# BATT_INPUT.net
KiCad netlist of a schematic drawn in EAGLE
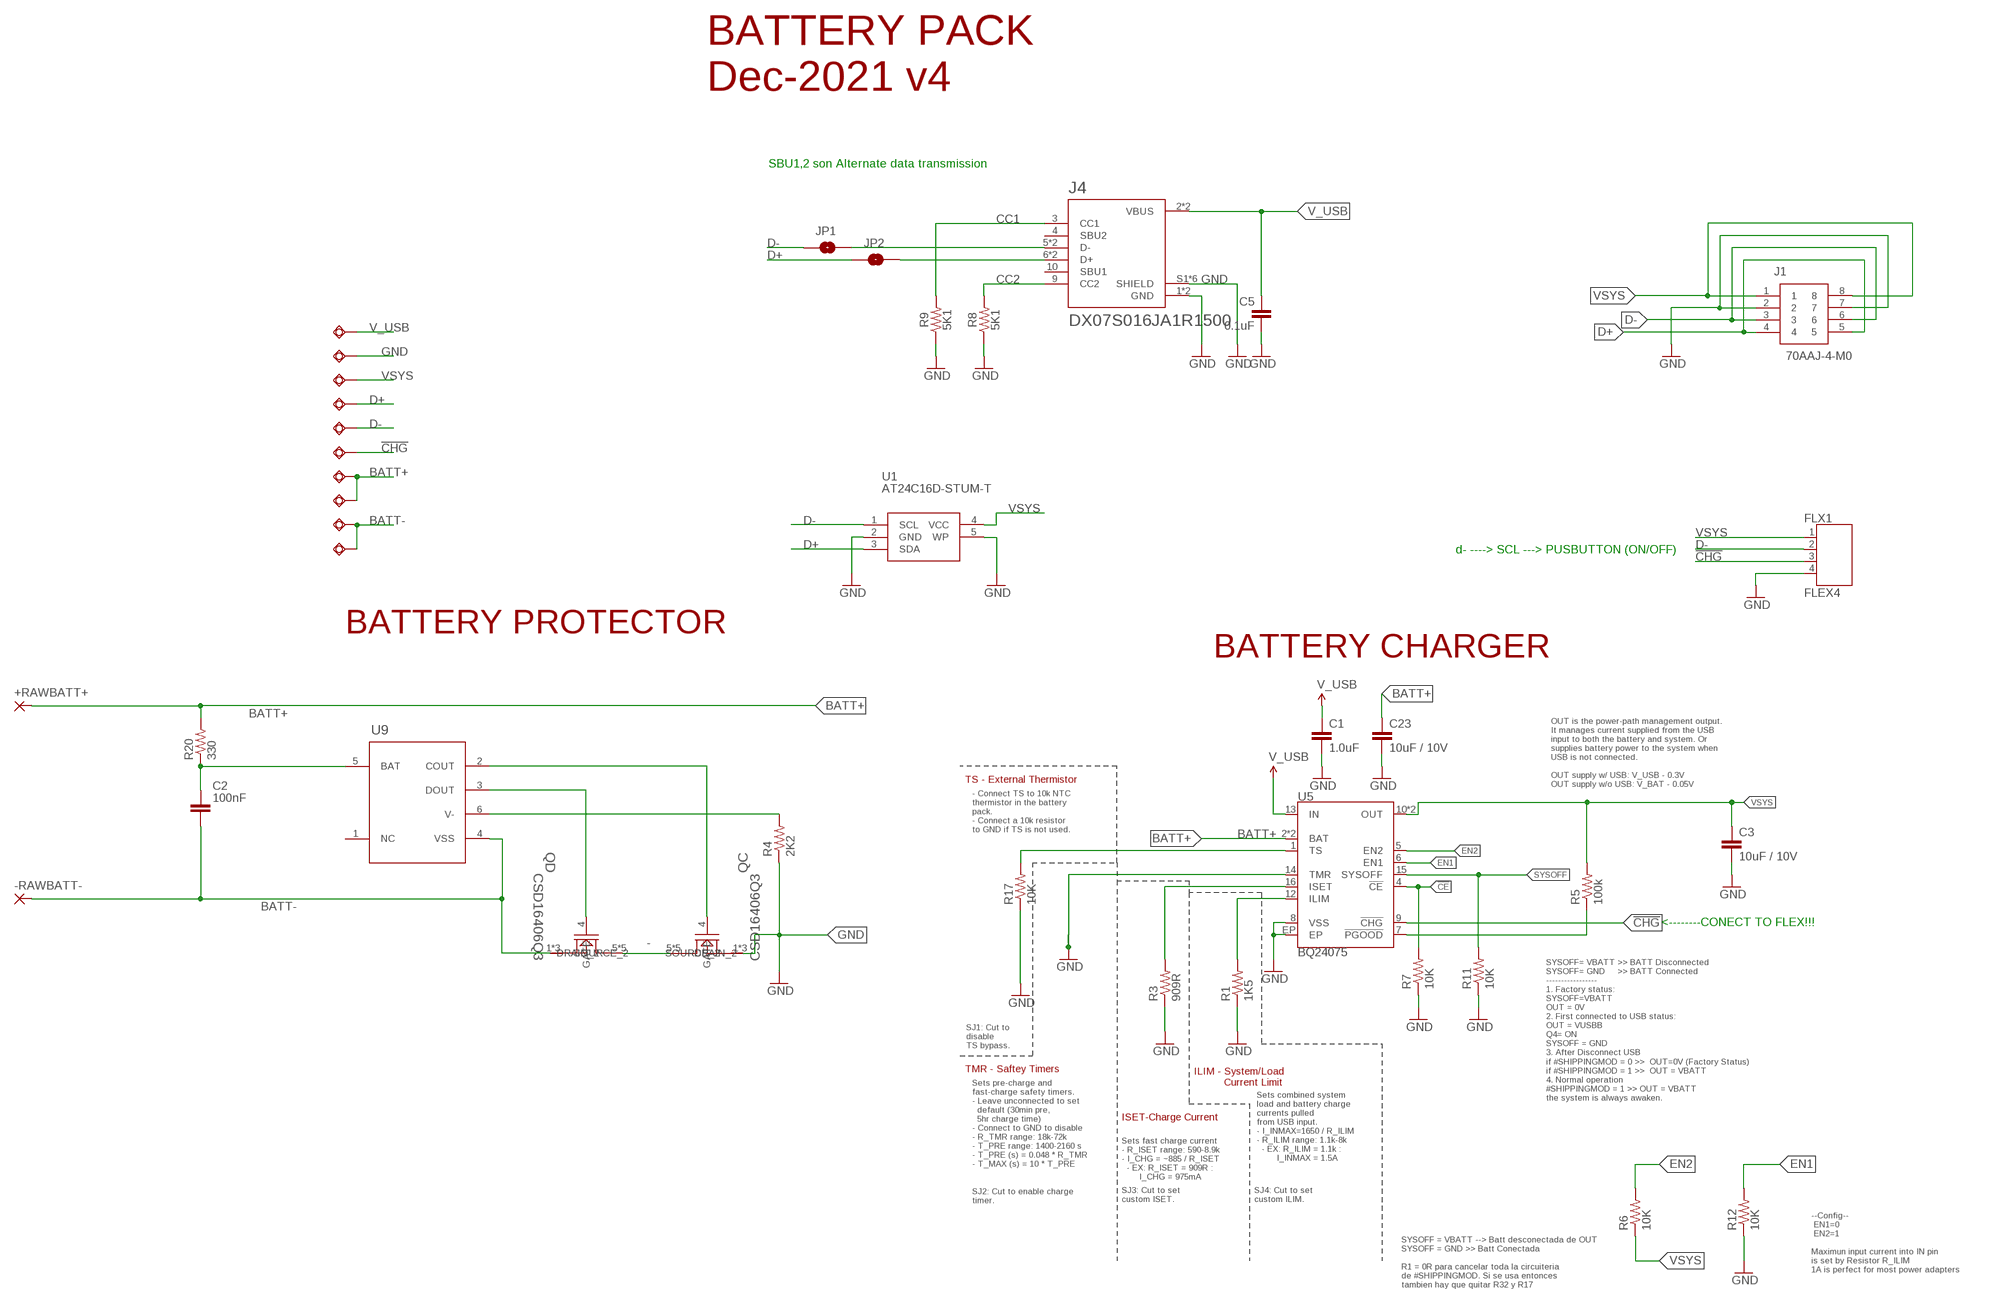
[diagram p0: schematic, sheet 1]

(export (version "E")
  (design (tool "Eeschema 10.0.6"))
  (components
    (comp (ref "!CHG!")
      (value "TESTPAD_TPSQB1,27")
      (footprint "eagle-import:TESTPAD_B1,27")
      (libsource (lib "eagle-import") (part "TESTPAD_TPSQB1,27"))
    )
    (comp (ref "+RAWBATT+")
      (value "SMD5")
      (footprint "eagle-import:SMD2,54-5,08")
      (libsource (lib "eagle-import") (part "SMD5"))
    )
    (comp (ref "-RAWBATT-")
      (value "SMD5")
      (footprint "eagle-import:SMD2,54-5,08")
      (libsource (lib "eagle-import") (part "SMD5"))
    )
    (comp (ref "BATT+1")
      (value "TESTPAD_TPSQB1,27")
      (footprint "eagle-import:TESTPAD_B1,27")
      (libsource (lib "eagle-import") (part "TESTPAD_TPSQB1,27"))
    )
    (comp (ref "BATT+2")
      (value "TESTPAD_TPSQB1,27")
      (footprint "eagle-import:TESTPAD_B1,27")
      (libsource (lib "eagle-import") (part "TESTPAD_TPSQB1,27"))
    )
    (comp (ref "BATT-1")
      (value "TESTPAD_TPSQB1,27")
      (footprint "eagle-import:TESTPAD_B1,27")
      (libsource (lib "eagle-import") (part "TESTPAD_TPSQB1,27"))
    )
    (comp (ref "BATT-2")
      (value "TESTPAD_TPSQB1,27")
      (footprint "eagle-import:TESTPAD_B1,27")
      (libsource (lib "eagle-import") (part "TESTPAD_TPSQB1,27"))
    )
    (comp (ref "C1")
      (value "1.0uF")
      (footprint "eagle-import:0603")
      (libsource (lib "eagle-import") (part "1.0UF-0603-16V-10%"))
    )
    (comp (ref "C2")
      (value "100nF")
      (footprint "eagle-import:CAPC1608X85")
      (libsource (lib "eagle-import") (part "CCHIP-0603(1608-METRIC)_"))
    )
    (comp (ref "C3")
      (value "10uF / 10V")
      (footprint "eagle-import:0805-CAP")
      (libsource (lib "eagle-import") (part "10UF10V10%(0805)"))
    )
    (comp (ref "C5")
      (value "0.1uF")
      (footprint "eagle-import:0603")
      (libsource (lib "eagle-import") (part "0.1UF-0603-25V-(+80/-20%)"))
    )
    (comp (ref "C23")
      (value "10uF / 10V")
      (footprint "eagle-import:0805-CAP")
      (libsource (lib "eagle-import") (part "10UF10V10%(0805)"))
    )
    (comp (ref "D+")
      (value "TESTPAD_TPSQB1,27")
      (footprint "eagle-import:TESTPAD_B1,27")
      (libsource (lib "eagle-import") (part "TESTPAD_TPSQB1,27"))
    )
    (comp (ref "D-")
      (value "TESTPAD_TPSQB1,27")
      (footprint "eagle-import:TESTPAD_B1,27")
      (libsource (lib "eagle-import") (part "TESTPAD_TPSQB1,27"))
    )
    (comp (ref "FLX1")
      (value "FLEX4")
      (footprint "eagle-import:FLEX4")
      (libsource (lib "eagle-import") (part "FLEX4"))
    )
    (comp (ref "GND")
      (value "TESTPAD_TPSQB1,27")
      (footprint "eagle-import:TESTPAD_B1,27")
      (libsource (lib "eagle-import") (part "TESTPAD_TPSQB1,27"))
    )
    (comp (ref "J1")
      (value "70AAJ-4-M0")
      (footprint "eagle-import:70AAJ4M0")
      (fields (field (name "MOUSER_PART_NUMBER") "652-70AAJ-4-M0"))
      (libsource (lib "eagle-import") (part "70AAJ-4-M0"))
    )
    (comp (ref "J4")
      (value "DX07S016JA1R1500")
      (footprint "eagle-import:JAE_DX07S016JA1R1500")
      (fields
        (field (name "DIGI-KEY_PART_NUMBER") "670-DX07S016JA1R1500CT-ND")
        (field (name "MF") "JAE Electronics")
      )
      (libsource (lib "eagle-import") (part "DX07S016JA1R1500"))
    )
    (comp (ref "JP1")
      (value "JUMPER-SMT_2_NO_SILK")
      (footprint "eagle-import:SMT-JUMPER_2_NO_SILK")
      (libsource (lib "eagle-import") (part "JUMPER-SMT_2_NO_SILK"))
    )
    (comp (ref "JP2")
      (value "JUMPER-SMT_2_NO_SILK")
      (footprint "eagle-import:SMT-JUMPER_2_NO_SILK")
      (libsource (lib "eagle-import") (part "JUMPER-SMT_2_NO_SILK"))
    )
    (comp (ref "QC")
      (value "CSD16406Q3")
      (footprint "eagle-import:DQG0008A")
      (libsource (lib "eagle-import") (part "CSD16406Q3"))
    )
    (comp (ref "QD")
      (value "CSD16406Q3")
      (footprint "eagle-import:DQG0008A")
      (libsource (lib "eagle-import") (part "CSD16406Q3"))
    )
    (comp (ref "R1")
      (value "1K5")
      (footprint "eagle-import:0402")
      (libsource (lib "eagle-import") (part "RESISTOR0402"))
    )
    (comp (ref "R3")
      (value "909R")
      (footprint "eagle-import:0402")
      (libsource (lib "eagle-import") (part "RESISTOR0402"))
    )
    (comp (ref "R4")
      (value "2K2")
      (footprint "eagle-import:0402")
      (libsource (lib "eagle-import") (part "RESISTOR0402"))
    )
    (comp (ref "R5")
      (value "100k")
      (footprint "eagle-import:0402")
      (libsource (lib "eagle-import") (part "RESISTOR0402"))
    )
    (comp (ref "R6")
      (value "10K")
      (footprint "eagle-import:0402")
      (libsource (lib "eagle-import") (part "RESISTOR0402"))
    )
    (comp (ref "R7")
      (value "10K")
      (footprint "eagle-import:0402")
      (libsource (lib "eagle-import") (part "RESISTOR0402"))
    )
    (comp (ref "R8")
      (value "5K1")
      (footprint "eagle-import:0402")
      (libsource (lib "eagle-import") (part "RESISTOR0402"))
    )
    (comp (ref "R9")
      (value "5K1")
      (footprint "eagle-import:0402")
      (libsource (lib "eagle-import") (part "RESISTOR0402"))
    )
    (comp (ref "R11")
      (value "10K")
      (footprint "eagle-import:0402")
      (libsource (lib "eagle-import") (part "RESISTOR0402"))
    )
    (comp (ref "R12")
      (value "10K")
      (footprint "eagle-import:0402")
      (libsource (lib "eagle-import") (part "RESISTOR0402"))
    )
    (comp (ref "R17")
      (value "10K")
      (footprint "eagle-import:0402")
      (libsource (lib "eagle-import") (part "RESISTOR0402"))
    )
    (comp (ref "R20")
      (value "330")
      (footprint "eagle-import:0402")
      (libsource (lib "eagle-import") (part "RESISTOR0402"))
    )
    (comp (ref "U1")
      (value "AT24C16D-STUM-T")
      (footprint "eagle-import:SOT95P280X100-5N")
      (fields (field (name "MOUSER_PART_NUMBER") "556-AT24C16D-STUM-T"))
      (libsource (lib "eagle-import") (part "AT24C16D-STUM-T"))
    )
    (comp (ref "U5")
      (value "BQ24075")
      (footprint "eagle-import:PVQFN-N16")
      (libsource (lib "eagle-import") (part "BQ24075"))
    )
    (comp (ref "U9")
      (value "BQ29700DSER")
      (footprint "eagle-import:DSE0006A")
      (fields (field (name "MANUFACTURER") "Texas Instruments") (field (name "PARTNUMBER") "BQ29705DSER"))
      (libsource (lib "eagle-import") (part "BQ29700DSER"))
    )
    (comp (ref "VSYS")
      (value "TESTPAD_TPSQB1,27")
      (footprint "eagle-import:TESTPAD_B1,27")
      (libsource (lib "eagle-import") (part "TESTPAD_TPSQB1,27"))
    )
    (comp (ref "V_USB")
      (value "TESTPAD_TPSQB1,27")
      (footprint "eagle-import:TESTPAD_B1,27")
      (libsource (lib "eagle-import") (part "TESTPAD_TPSQB1,27"))
    )
  )
  (nets
    (net (code "1") (name "/-") (class "Default")
      (node (ref "QC") (pin "5") (pinfunction "DRAIN_2_5") (pintype "passive"))
      (node (ref "QC") (pin "6") (pinfunction "DRAIN_2_6") (pintype "passive"))
      (node (ref "QC") (pin "7") (pinfunction "DRAIN_2_7") (pintype "passive"))
      (node (ref "QC") (pin "8") (pinfunction "DRAIN_2_8") (pintype "passive"))
      (node (ref "QC") (pin "9") (pinfunction "DRAIN_2_9") (pintype "passive"))
      (node (ref "QD") (pin "5") (pinfunction "DRAIN_2_5") (pintype "passive"))
      (node (ref "QD") (pin "6") (pinfunction "DRAIN_2_6") (pintype "passive"))
      (node (ref "QD") (pin "7") (pinfunction "DRAIN_2_7") (pintype "passive"))
      (node (ref "QD") (pin "8") (pinfunction "DRAIN_2_8") (pintype "passive"))
      (node (ref "QD") (pin "9") (pinfunction "DRAIN_2_9") (pintype "passive"))
    )
    (net (code "2") (name "/BATT-") (class "Default")
      (node (ref "-RAWBATT-") (pin "1") (pinfunction "P_1") (pintype "passive"))
      (node (ref "BATT-1") (pin "TP") (pinfunction "TP_TP") (pintype "input"))
      (node (ref "BATT-2") (pin "TP") (pinfunction "TP_TP") (pintype "input"))
      (node (ref "C2") (pin "2") (pinfunction "2_2") (pintype "passive"))
      (node (ref "QD") (pin "1") (pinfunction "SOURCE_2_1") (pintype "passive"))
      (node (ref "QD") (pin "2") (pinfunction "SOURCE_2_2") (pintype "passive"))
      (node (ref "QD") (pin "3") (pinfunction "SOURCE_2_3") (pintype "passive"))
      (node (ref "U9") (pin "4") (pinfunction "VSS_4") (pintype "power_in"))
    )
    (net (code "3") (name "/CC1") (class "Default")
      (node (ref "J4") (pin "3") (pinfunction "CC1_3") (pintype "passive"))
      (node (ref "R9") (pin "2") (pinfunction "2_2") (pintype "passive"))
    )
    (net (code "4") (name "/CC2") (class "Default")
      (node (ref "J4") (pin "9") (pinfunction "CC2_9") (pintype "passive"))
      (node (ref "R8") (pin "2") (pinfunction "2_2") (pintype "passive"))
    )
    (net (code "5") (name "/~{CE}") (class "Default")
      (node (ref "R7") (pin "2") (pinfunction "2_2") (pintype "passive"))
      (node (ref "U5") (pin "4") (pinfunction "~{CE}_4") (pintype "bidirectional"))
    )
    (net (code "6") (name "/~{CHG}") (class "Default")
      (node (ref "!CHG!") (pin "TP") (pinfunction "TP_TP") (pintype "input"))
      (node (ref "FLX1") (pin "3") (pinfunction "3_3") (pintype "passive"))
      (node (ref "U5") (pin "9") (pinfunction "~{CHG}_9") (pintype "bidirectional"))
    )
    (net (code "7") (name "BATT+") (class "Default")
      (node (ref "+RAWBATT+") (pin "1") (pinfunction "P_1") (pintype "passive"))
      (node (ref "BATT+1") (pin "TP") (pinfunction "TP_TP") (pintype "input"))
      (node (ref "BATT+2") (pin "TP") (pinfunction "TP_TP") (pintype "input"))
      (node (ref "C23") (pin "1") (pinfunction "1_1") (pintype "passive"))
      (node (ref "R20") (pin "2") (pinfunction "2_2") (pintype "passive"))
      (node (ref "U5") (pin "2") (pinfunction "BAT_2") (pintype "bidirectional"))
      (node (ref "U5") (pin "3") (pinfunction "BAT_3") (pintype "bidirectional"))
    )
    (net (code "8") (name "D+") (class "Default")
      (node (ref "D+") (pin "TP") (pinfunction "TP_TP") (pintype "input"))
      (node (ref "J1") (pin "4") (pinfunction "4_4") (pintype "bidirectional"))
      (node (ref "J1") (pin "5") (pinfunction "5_5") (pintype "bidirectional"))
      (node (ref "JP2") (pin "1") (pinfunction "1_1") (pintype "passive"))
      (node (ref "U1") (pin "3") (pinfunction "SDA_3") (pintype "bidirectional"))
    )
    (net (code "9") (name "D-") (class "Default")
      (node (ref "D-") (pin "TP") (pinfunction "TP_TP") (pintype "input"))
      (node (ref "FLX1") (pin "2") (pinfunction "2_2") (pintype "passive"))
      (node (ref "J1") (pin "3") (pinfunction "3_3") (pintype "bidirectional"))
      (node (ref "J1") (pin "6") (pinfunction "6_6") (pintype "bidirectional"))
      (node (ref "JP1") (pin "1") (pinfunction "1_1") (pintype "passive"))
      (node (ref "U1") (pin "1") (pinfunction "SCL_1") (pintype "bidirectional"))
    )
    (net (code "10") (name "EN1") (class "Default")
      (node (ref "R12") (pin "2") (pinfunction "2_2") (pintype "passive"))
      (node (ref "U5") (pin "6") (pinfunction "EN1_6") (pintype "bidirectional"))
    )
    (net (code "11") (name "EN2") (class "Default")
      (node (ref "R6") (pin "2") (pinfunction "2_2") (pintype "passive"))
      (node (ref "U5") (pin "5") (pinfunction "EN2_5") (pintype "bidirectional"))
    )
    (net (code "12") (name "GND") (class "Default")
      (node (ref "C1") (pin "2") (pinfunction "2_2") (pintype "passive"))
      (node (ref "C23") (pin "2") (pinfunction "2_2") (pintype "passive"))
      (node (ref "C3") (pin "2") (pinfunction "2_2") (pintype "passive"))
      (node (ref "C5") (pin "2") (pinfunction "2_2") (pintype "passive"))
      (node (ref "FLX1") (pin "4") (pinfunction "4_4") (pintype "passive"))
      (node (ref "GND") (pin "TP") (pinfunction "TP_TP") (pintype "input"))
      (node (ref "J1") (pin "2") (pinfunction "2_2") (pintype "bidirectional"))
      (node (ref "J1") (pin "7") (pinfunction "7_7") (pintype "bidirectional"))
      (node (ref "J4") (pin "1") (pinfunction "GND_1") (pintype "power_in"))
      (node (ref "J4") (pin "12") (pinfunction "GND_12") (pintype "power_in"))
      (node (ref "J4") (pin "S1") (pinfunction "SHIELD_S1") (pintype "passive"))
      (node (ref "J4") (pin "S2") (pinfunction "SHIELD_S2") (pintype "passive"))
      (node (ref "J4") (pin "S3") (pinfunction "SHIELD_S3") (pintype "passive"))
      (node (ref "J4") (pin "S4") (pinfunction "SHIELD_S4") (pintype "passive"))
      (node (ref "J4") (pin "S5") (pinfunction "SHIELD_S5") (pintype "passive"))
      (node (ref "J4") (pin "S6") (pinfunction "SHIELD_S6") (pintype "passive"))
      (node (ref "QC") (pin "1") (pinfunction "SOURCE_2_1") (pintype "passive"))
      (node (ref "QC") (pin "2") (pinfunction "SOURCE_2_2") (pintype "passive"))
      (node (ref "QC") (pin "3") (pinfunction "SOURCE_2_3") (pintype "passive"))
      (node (ref "R1") (pin "1") (pinfunction "1_1") (pintype "passive"))
      (node (ref "R11") (pin "1") (pinfunction "1_1") (pintype "passive"))
      (node (ref "R12") (pin "1") (pinfunction "1_1") (pintype "passive"))
      (node (ref "R17") (pin "1") (pinfunction "1_1") (pintype "passive"))
      (node (ref "R3") (pin "1") (pinfunction "1_1") (pintype "passive"))
      (node (ref "R4") (pin "1") (pinfunction "1_1") (pintype "passive"))
      (node (ref "R7") (pin "1") (pinfunction "1_1") (pintype "passive"))
      (node (ref "R8") (pin "1") (pinfunction "1_1") (pintype "passive"))
      (node (ref "R9") (pin "1") (pinfunction "1_1") (pintype "passive"))
      (node (ref "U1") (pin "2") (pinfunction "GND_2") (pintype "power_in"))
      (node (ref "U1") (pin "5") (pinfunction "WP_5") (pintype "input"))
      (node (ref "U5") (pin "14") (pinfunction "TMR_14") (pintype "bidirectional"))
      (node (ref "U5") (pin "8") (pinfunction "VSS_8") (pintype "bidirectional"))
      (node (ref "U5") (pin "EP") (pinfunction "EP_EP") (pintype "bidirectional"))
    )
    (net (code "13") (name "Net-(J4-D+-Pad6)") (class "Default")
      (node (ref "J4") (pin "6") (pinfunction "D+_6") (pintype "passive"))
      (node (ref "J4") (pin "7") (pinfunction "D+_7") (pintype "passive"))
      (node (ref "JP2") (pin "2") (pinfunction "2_2") (pintype "passive"))
    )
    (net (code "14") (name "Net-(J4-D--Pad5)") (class "Default")
      (node (ref "J4") (pin "5") (pinfunction "D-_5") (pintype "passive"))
      (node (ref "J4") (pin "8") (pinfunction "D-_8") (pintype "passive"))
      (node (ref "JP1") (pin "2") (pinfunction "2_2") (pintype "passive"))
    )
    (net (code "15") (name "Net-(QC-GATE)") (class "Default")
      (node (ref "QC") (pin "4") (pinfunction "GATE_4") (pintype "passive"))
      (node (ref "U9") (pin "2") (pinfunction "COUT_2") (pintype "output"))
    )
    (net (code "16") (name "Net-(QD-GATE)") (class "Default")
      (node (ref "QD") (pin "4") (pinfunction "GATE_4") (pintype "passive"))
      (node (ref "U9") (pin "3") (pinfunction "DOUT_3") (pintype "output"))
    )
    (net (code "17") (name "Net-(U5-ILIM)") (class "Default")
      (node (ref "R1") (pin "2") (pinfunction "2_2") (pintype "passive"))
      (node (ref "U5") (pin "12") (pinfunction "ILIM_12") (pintype "bidirectional"))
    )
    (net (code "18") (name "Net-(U5-ISET)") (class "Default")
      (node (ref "R3") (pin "2") (pinfunction "2_2") (pintype "passive"))
      (node (ref "U5") (pin "16") (pinfunction "ISET_16") (pintype "bidirectional"))
    )
    (net (code "19") (name "Net-(U5-TS)") (class "Default")
      (node (ref "R17") (pin "2") (pinfunction "2_2") (pintype "passive"))
      (node (ref "U5") (pin "1") (pinfunction "TS_1") (pintype "bidirectional"))
    )
    (net (code "20") (name "Net-(U5-~{PGOOD})") (class "Default")
      (node (ref "R5") (pin "1") (pinfunction "1_1") (pintype "passive"))
      (node (ref "U5") (pin "7") (pinfunction "~{PGOOD}_7") (pintype "bidirectional"))
    )
    (net (code "21") (name "Net-(U9-BAT)") (class "Default")
      (node (ref "C2") (pin "1") (pinfunction "1_1") (pintype "passive"))
      (node (ref "R20") (pin "1") (pinfunction "1_1") (pintype "passive"))
      (node (ref "U9") (pin "5") (pinfunction "BAT_5") (pintype "power_in"))
    )
    (net (code "22") (name "Net-(U9-V-)") (class "Default")
      (node (ref "R4") (pin "2") (pinfunction "2_2") (pintype "passive"))
      (node (ref "U9") (pin "6") (pinfunction "V-_6") (pintype "bidirectional"))
    )
    (net (code "23") (name "SYSOFF") (class "Default")
      (node (ref "R11") (pin "2") (pinfunction "2_2") (pintype "passive"))
      (node (ref "U5") (pin "15") (pinfunction "SYSOFF_15") (pintype "bidirectional"))
    )
    (net (code "24") (name "VSYS") (class "Default")
      (node (ref "C3") (pin "1") (pinfunction "1_1") (pintype "passive"))
      (node (ref "FLX1") (pin "1") (pinfunction "1_1") (pintype "passive"))
      (node (ref "J1") (pin "1") (pinfunction "1_1") (pintype "bidirectional"))
      (node (ref "J1") (pin "8") (pinfunction "8_8") (pintype "bidirectional"))
      (node (ref "R5") (pin "2") (pinfunction "2_2") (pintype "passive"))
      (node (ref "R6") (pin "1") (pinfunction "1_1") (pintype "passive"))
      (node (ref "U1") (pin "4") (pinfunction "VCC_4") (pintype "power_in"))
      (node (ref "U5") (pin "10") (pinfunction "OUT_10") (pintype "bidirectional"))
      (node (ref "U5") (pin "11") (pinfunction "OUT_11") (pintype "bidirectional"))
      (node (ref "VSYS") (pin "TP") (pinfunction "TP_TP") (pintype "input"))
    )
    (net (code "25") (name "V_USB") (class "Default")
      (node (ref "C1") (pin "1") (pinfunction "1_1") (pintype "passive"))
      (node (ref "C5") (pin "1") (pinfunction "1_1") (pintype "passive"))
      (node (ref "J4") (pin "11") (pinfunction "VBUS_11") (pintype "power_in"))
      (node (ref "J4") (pin "2") (pinfunction "VBUS_2") (pintype "power_in"))
      (node (ref "U5") (pin "13") (pinfunction "IN_13") (pintype "bidirectional"))
      (node (ref "V_USB") (pin "TP") (pinfunction "TP_TP") (pintype "input"))
    )
    (net (code "26") (name "unconnected-(J4-SBU1-Pad10)") (class "Default")
      (node (ref "J4") (pin "10") (pinfunction "SBU1_10") (pintype "passive"))
    )
    (net (code "27") (name "unconnected-(J4-SBU2-Pad4)") (class "Default")
      (node (ref "J4") (pin "4") (pinfunction "SBU2_4") (pintype "passive"))
    )
    (net (code "28") (name "unconnected-(U9-NC-Pad1)") (class "Default")
      (node (ref "U9") (pin "1") (pinfunction "NC_1") (pintype "passive"))
    )
  )
)
